# WiFiPassThrogh.net
KiCad netlist of a schematic drawn in Altium Designer
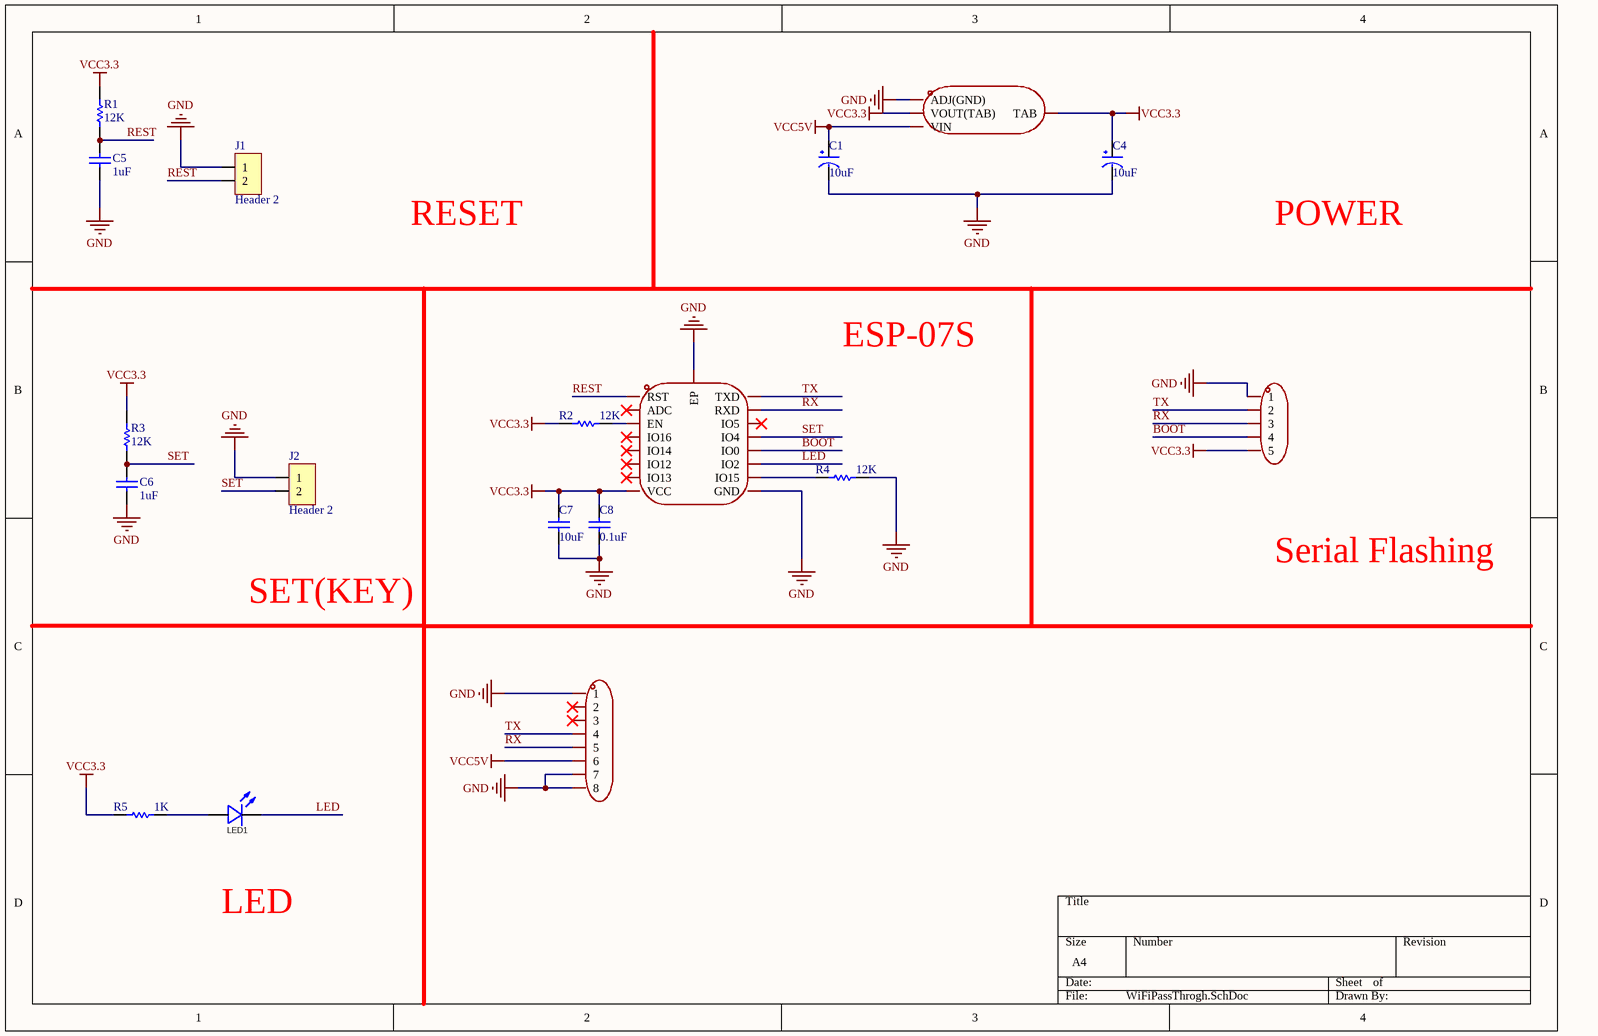
[diagram p0: WiFiPassThrogh.SchDoc]

(export (version "E")
  (design (tool "Eeschema 10.0.6"))
  (components
    (comp (ref "C1")
      (value "10uF")
      (footprint "CAP-SMD_L3.2-W1.6-RD-C7171")
      (description "极性电容")
      (libsource (lib "yhjtzz") (part "Cap Pol"))
    )
    (comp (ref "C4")
      (value "10uF")
      (footprint "CAP-SMD_L3.2-W1.6-RD-C7171")
      (description "极性电容")
      (libsource (lib "yhjtzz") (part "Cap Pol"))
    )
    (comp (ref "C5")
      (value "1uF")
      (footprint "C0805")
      (description "电容")
      (fields (field (name "PUBLISHER") "Altium Limited"))
      (libsource (lib "yhjtzz") (part "Cap"))
    )
    (comp (ref "C6")
      (value "1uF")
      (footprint "C0805")
      (description "电容")
      (fields (field (name "PUBLISHER") "Altium Limited"))
      (libsource (lib "yhjtzz") (part "Cap"))
    )
    (comp (ref "C7")
      (value "10uF")
      (footprint "C0805")
      (description "电容")
      (fields (field (name "PUBLISHER") "Altium Limited"))
      (libsource (lib "yhjtzz") (part "Cap"))
    )
    (comp (ref "C8")
      (value "0.1uF")
      (footprint "C0805")
      (description "电容")
      (fields (field (name "PUBLISHER") "Altium Limited"))
      (libsource (lib "yhjtzz") (part "Cap"))
    )
    (comp (ref "CON1")
      (value "HC-1.25-6PWT")
      (footprint "CONN-SMD_6P-P1.25_HC-1.25-6PWT")
      (fields (field (name "MANUFACTURER") "HCTL(华灿天禄)"))
      (libsource (lib "yhjtzz") (part "HC-1.25-6PWT"))
    )
    (comp (ref "J1")
      (value "Header 2")
      (footprint "HDR-TH_2P-P2.54-V-M")
      (description "Header, 2-Pin")
      (fields (field (name "PUBLISHER") "Altium Limited"))
      (libsource (lib "yhjtzz") (part "Header 2"))
    )
    (comp (ref "J2")
      (value "Header 2")
      (footprint "HDR-TH_2P-P2.54-V-M")
      (description "Header, 2-Pin")
      (fields (field (name "PUBLISHER") "Altium Limited"))
      (libsource (lib "yhjtzz") (part "Header 2"))
    )
    (comp (ref "J3")
      (value "PZ254V-11-05P")
      (footprint "HDR-TH_5P-P2.54-V-M")
      (fields (field (name "MANUFACTURER") "XFCN(兴飞)"))
      (libsource (lib "yhjtzz") (part "Header 5"))
    )
    (comp (ref "LED1")
      (value "NCD0805R1")
      (footprint "LED0805-R-RD")
      (fields (field (name "MANUFACTURER") "国星光电"))
      (libsource (lib "yhjtzz") (part "LED0805R1"))
    )
    (comp (ref "R1")
      (value "12K")
      (footprint "R0805")
      (description "电阻")
      (fields (field (name "PUBLISHER") "Altium Limited"))
      (libsource (lib "yhjtzz") (part "Res1"))
    )
    (comp (ref "R2")
      (value "12K")
      (footprint "R0805")
      (description "电阻")
      (fields (field (name "PUBLISHER") "Altium Limited"))
      (libsource (lib "yhjtzz") (part "Res1"))
    )
    (comp (ref "R3")
      (value "12K")
      (footprint "R0805")
      (description "电阻")
      (fields (field (name "PUBLISHER") "Altium Limited"))
      (libsource (lib "yhjtzz") (part "Res1"))
    )
    (comp (ref "R4")
      (value "12K")
      (footprint "R0805")
      (description "电阻")
      (fields (field (name "PUBLISHER") "Altium Limited"))
      (libsource (lib "yhjtzz") (part "Res1"))
    )
    (comp (ref "R5")
      (value "1K")
      (footprint "R0805")
      (description "电阻")
      (fields (field (name "PUBLISHER") "Altium Limited"))
      (libsource (lib "yhjtzz") (part "Res1"))
    )
    (comp (ref "U1")
      (value "AMS1117-3.3")
      (footprint "AMS1117-SOT-223-4")
      (fields (field (name "MANUFACTURER") "UMW(友台半导体)"))
      (libsource (lib "yhjtzz") (part "AMS1117-3.3_C347222"))
    )
    (comp (ref "U2")
      (value "ESP-07S")
      (footprint "WIRELM-SMD_ESP-07S")
      (description "ESP8266-07S")
      (fields (field (name "MANUFACTURER") "Ai-Thinker(安信可)"))
      (libsource (lib "yhjtzz") (part "ESP-07S"))
    )
  )
  (nets
    (net (code "1") (name "/BOOT") (class "Default")
      (node (ref "J3") (pin "4") (pinfunction "4_4") (pintype "passive"))
      (node (ref "U2") (pin "12") (pinfunction "IO0_12") (pintype "passive"))
    )
    (net (code "2") (name "/LED") (class "Default")
      (node (ref "LED1") (pin "2") (pinfunction "-_2") (pintype "passive"))
      (node (ref "U2") (pin "11") (pinfunction "IO2_11") (pintype "passive"))
    )
    (net (code "3") (name "/REST") (class "Default")
      (node (ref "C5") (pin "2") (pinfunction "2_2") (pintype "passive"))
      (node (ref "J1") (pin "2") (pinfunction "2_2") (pintype "passive"))
      (node (ref "R1") (pin "1") (pinfunction "1_1") (pintype "passive"))
      (node (ref "U2") (pin "1") (pinfunction "RST_1") (pintype "passive"))
    )
    (net (code "4") (name "/RX") (class "Default")
      (node (ref "CON1") (pin "5") (pinfunction "5_5") (pintype "passive"))
      (node (ref "J3") (pin "3") (pinfunction "3_3") (pintype "passive"))
      (node (ref "U2") (pin "15") (pinfunction "RXD_15") (pintype "passive"))
    )
    (net (code "5") (name "/SET") (class "Default")
      (node (ref "C6") (pin "2") (pinfunction "2_2") (pintype "passive"))
      (node (ref "J2") (pin "2") (pinfunction "2_2") (pintype "passive"))
      (node (ref "R3") (pin "1") (pinfunction "1_1") (pintype "passive"))
      (node (ref "U2") (pin "13") (pinfunction "IO4_13") (pintype "passive"))
    )
    (net (code "6") (name "/TX") (class "Default")
      (node (ref "CON1") (pin "4") (pinfunction "4_4") (pintype "passive"))
      (node (ref "J3") (pin "2") (pinfunction "2_2") (pintype "passive"))
      (node (ref "U2") (pin "16") (pinfunction "TXD_16") (pintype "passive"))
    )
    (net (code "7") (name "GND") (class "Default")
      (node (ref "C1") (pin "2") (pinfunction "GND_2") (pintype "passive"))
      (node (ref "C4") (pin "2") (pinfunction "GND_2") (pintype "passive"))
      (node (ref "C5") (pin "1") (pinfunction "1_1") (pintype "passive"))
      (node (ref "C6") (pin "1") (pinfunction "1_1") (pintype "passive"))
      (node (ref "C7") (pin "1") (pinfunction "1_1") (pintype "passive"))
      (node (ref "C8") (pin "1") (pinfunction "1_1") (pintype "passive"))
      (node (ref "CON1") (pin "1") (pinfunction "1_1") (pintype "passive"))
      (node (ref "CON1") (pin "7") (pinfunction "7_7") (pintype "passive"))
      (node (ref "CON1") (pin "8") (pinfunction "8_8") (pintype "passive"))
      (node (ref "J1") (pin "1") (pinfunction "1_1") (pintype "passive"))
      (node (ref "J2") (pin "1") (pinfunction "1_1") (pintype "passive"))
      (node (ref "J3") (pin "1") (pinfunction "1_1") (pintype "passive"))
      (node (ref "R4") (pin "2") (pinfunction "2_2") (pintype "passive"))
      (node (ref "U1") (pin "1") (pinfunction "ADJ(GND)_1") (pintype "passive"))
      (node (ref "U2") (pin "17") (pinfunction "EP_17") (pintype "passive"))
      (node (ref "U2") (pin "9") (pinfunction "GND_9") (pintype "passive"))
    )
    (net (code "8") (name "Net-(LED1-+)") (class "Default")
      (node (ref "LED1") (pin "1") (pinfunction "+_1") (pintype "passive"))
      (node (ref "R5") (pin "1") (pinfunction "1_1") (pintype "passive"))
    )
    (net (code "9") (name "Net-(U2-EN)") (class "Default")
      (node (ref "R2") (pin "2") (pinfunction "2_2") (pintype "passive"))
      (node (ref "U2") (pin "3") (pinfunction "EN_3") (pintype "passive"))
    )
    (net (code "10") (name "Net-(U2-IO15)") (class "Default")
      (node (ref "R4") (pin "1") (pinfunction "1_1") (pintype "passive"))
      (node (ref "U2") (pin "10") (pinfunction "IO15_10") (pintype "passive"))
    )
    (net (code "11") (name "VCC3.3") (class "Default")
      (node (ref "C4") (pin "1") (pinfunction "VCC_1") (pintype "passive"))
      (node (ref "C7") (pin "2") (pinfunction "2_2") (pintype "passive"))
      (node (ref "C8") (pin "2") (pinfunction "2_2") (pintype "passive"))
      (node (ref "J3") (pin "5") (pinfunction "5_5") (pintype "passive"))
      (node (ref "R1") (pin "2") (pinfunction "2_2") (pintype "passive"))
      (node (ref "R2") (pin "1") (pinfunction "1_1") (pintype "passive"))
      (node (ref "R3") (pin "2") (pinfunction "2_2") (pintype "passive"))
      (node (ref "R5") (pin "2") (pinfunction "2_2") (pintype "passive"))
      (node (ref "U1") (pin "2") (pinfunction "VOUT(TAB)_2") (pintype "passive"))
      (node (ref "U1") (pin "4") (pinfunction "TAB_4") (pintype "passive"))
      (node (ref "U2") (pin "8") (pinfunction "VCC_8") (pintype "passive"))
    )
    (net (code "12") (name "VCC5V") (class "Default")
      (node (ref "C1") (pin "1") (pinfunction "VCC_1") (pintype "passive"))
      (node (ref "CON1") (pin "6") (pinfunction "6_6") (pintype "passive"))
      (node (ref "U1") (pin "3") (pinfunction "VIN_3") (pintype "passive"))
    )
    (net (code "13") (name "unconnected-(CON1-Pad2)") (class "Default")
      (node (ref "CON1") (pin "2") (pinfunction "2_2") (pintype "passive+no_connect"))
    )
    (net (code "14") (name "unconnected-(CON1-Pad3)") (class "Default")
      (node (ref "CON1") (pin "3") (pinfunction "3_3") (pintype "passive+no_connect"))
    )
    (net (code "15") (name "unconnected-(U2-ADC-Pad2)") (class "Default")
      (node (ref "U2") (pin "2") (pinfunction "ADC_2") (pintype "passive+no_connect"))
    )
    (net (code "16") (name "unconnected-(U2-IO5-Pad14)") (class "Default")
      (node (ref "U2") (pin "14") (pinfunction "IO5_14") (pintype "passive+no_connect"))
    )
    (net (code "17") (name "unconnected-(U2-IO12-Pad6)") (class "Default")
      (node (ref "U2") (pin "6") (pinfunction "IO12_6") (pintype "passive+no_connect"))
    )
    (net (code "18") (name "unconnected-(U2-IO13-Pad7)") (class "Default")
      (node (ref "U2") (pin "7") (pinfunction "IO13_7") (pintype "passive+no_connect"))
    )
    (net (code "19") (name "unconnected-(U2-IO14-Pad5)") (class "Default")
      (node (ref "U2") (pin "5") (pinfunction "IO14_5") (pintype "passive+no_connect"))
    )
    (net (code "20") (name "unconnected-(U2-IO16-Pad4)") (class "Default")
      (node (ref "U2") (pin "4") (pinfunction "IO16_4") (pintype "passive+no_connect"))
    )
  )
)
